# untitled.net
KiCad netlist of a schematic drawn in EAGLE
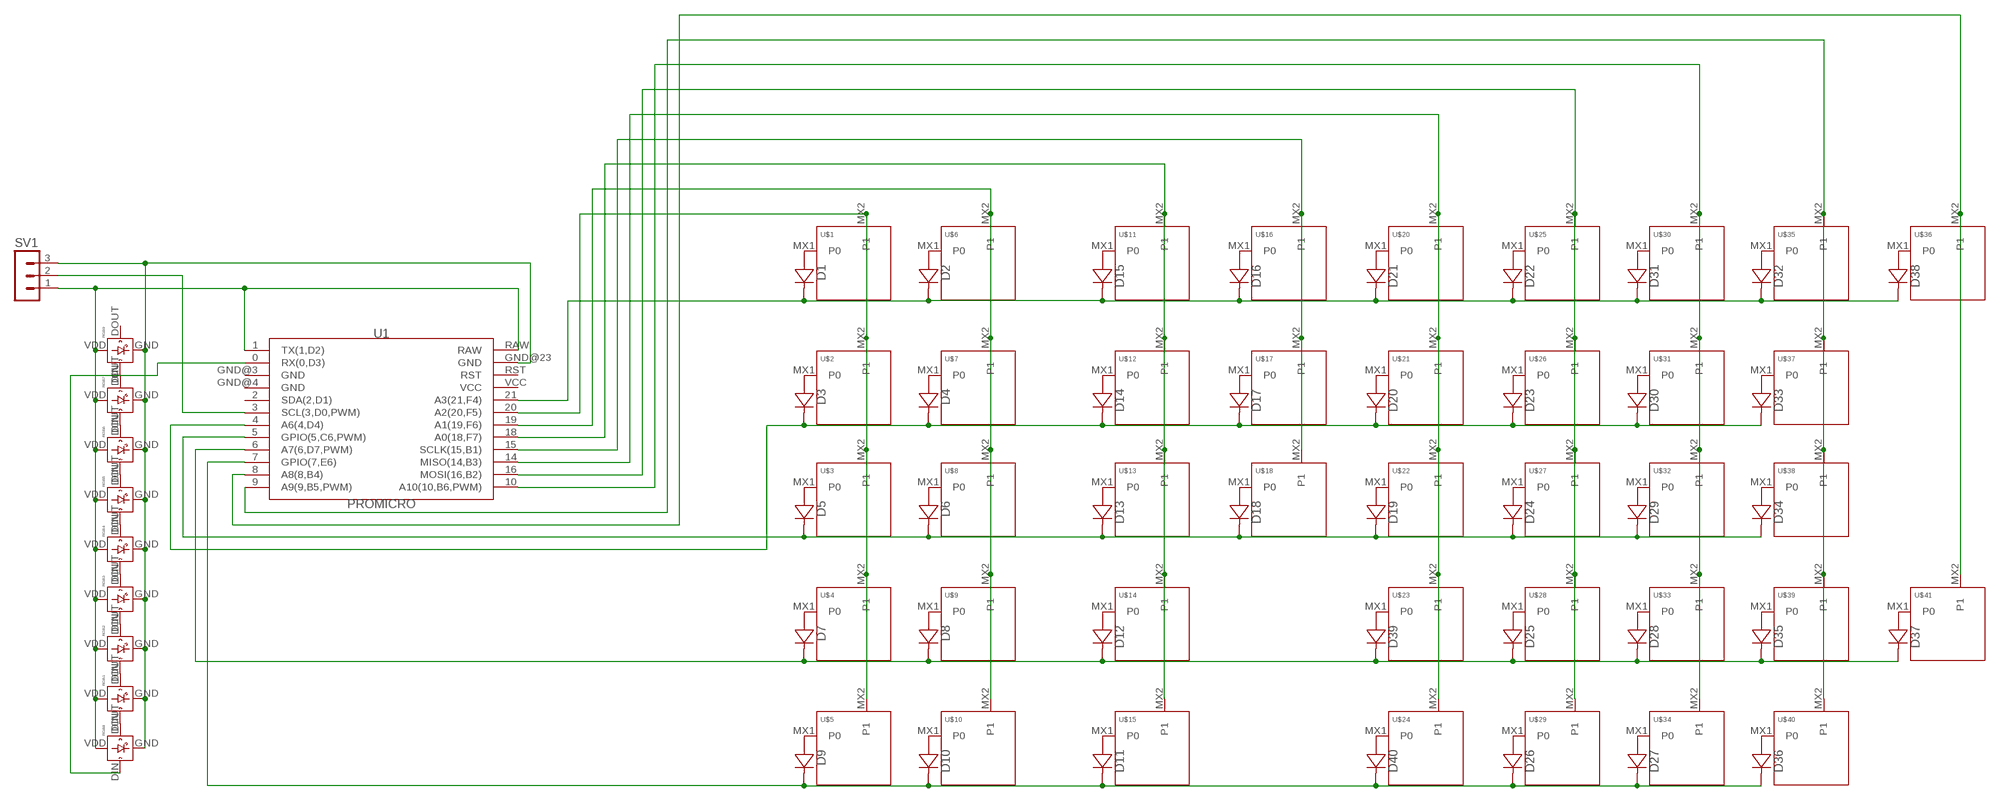
[diagram p0: schematic, sheet 1]

(export (version "E")
  (design (tool "Eeschema 10.0.6"))
  (components
    (comp (ref "D1")
      (value "DIODE-SOD-123")
      (footprint "eagle-import:SOD-123")
      (libsource (lib "eagle-import") (part "DIODE-SOD-123"))
    )
    (comp (ref "D2")
      (value "DIODE-SOD-123")
      (footprint "eagle-import:SOD-123")
      (libsource (lib "eagle-import") (part "DIODE-SOD-123"))
    )
    (comp (ref "D3")
      (value "DIODE-SOD-123")
      (footprint "eagle-import:SOD-123")
      (libsource (lib "eagle-import") (part "DIODE-SOD-123"))
    )
    (comp (ref "D4")
      (value "DIODE-SOD-123")
      (footprint "eagle-import:SOD-123")
      (libsource (lib "eagle-import") (part "DIODE-SOD-123"))
    )
    (comp (ref "D5")
      (value "DIODE-SOD-123")
      (footprint "eagle-import:SOD-123")
      (libsource (lib "eagle-import") (part "DIODE-SOD-123"))
    )
    (comp (ref "D6")
      (value "DIODE-SOD-123")
      (footprint "eagle-import:SOD-123")
      (libsource (lib "eagle-import") (part "DIODE-SOD-123"))
    )
    (comp (ref "D7")
      (value "DIODE-SOD-123")
      (footprint "eagle-import:SOD-123")
      (libsource (lib "eagle-import") (part "DIODE-SOD-123"))
    )
    (comp (ref "D8")
      (value "DIODE-SOD-123")
      (footprint "eagle-import:SOD-123")
      (libsource (lib "eagle-import") (part "DIODE-SOD-123"))
    )
    (comp (ref "D9")
      (value "DIODE-SOD-123")
      (footprint "eagle-import:SOD-123")
      (libsource (lib "eagle-import") (part "DIODE-SOD-123"))
    )
    (comp (ref "D10")
      (value "DIODE-SOD-123")
      (footprint "eagle-import:SOD-123")
      (libsource (lib "eagle-import") (part "DIODE-SOD-123"))
    )
    (comp (ref "D11")
      (value "DIODE-SOD-123")
      (footprint "eagle-import:SOD-123")
      (libsource (lib "eagle-import") (part "DIODE-SOD-123"))
    )
    (comp (ref "D12")
      (value "DIODE-SOD-123")
      (footprint "eagle-import:SOD-123")
      (libsource (lib "eagle-import") (part "DIODE-SOD-123"))
    )
    (comp (ref "D13")
      (value "DIODE-SOD-123")
      (footprint "eagle-import:SOD-123")
      (libsource (lib "eagle-import") (part "DIODE-SOD-123"))
    )
    (comp (ref "D14")
      (value "DIODE-SOD-123")
      (footprint "eagle-import:SOD-123")
      (libsource (lib "eagle-import") (part "DIODE-SOD-123"))
    )
    (comp (ref "D15")
      (value "DIODE-SOD-123")
      (footprint "eagle-import:SOD-123")
      (libsource (lib "eagle-import") (part "DIODE-SOD-123"))
    )
    (comp (ref "D16")
      (value "DIODE-SOD-123")
      (footprint "eagle-import:SOD-123")
      (libsource (lib "eagle-import") (part "DIODE-SOD-123"))
    )
    (comp (ref "D17")
      (value "DIODE-SOD-123")
      (footprint "eagle-import:SOD-123")
      (libsource (lib "eagle-import") (part "DIODE-SOD-123"))
    )
    (comp (ref "D18")
      (value "DIODE-SOD-123")
      (footprint "eagle-import:SOD-123")
      (libsource (lib "eagle-import") (part "DIODE-SOD-123"))
    )
    (comp (ref "D19")
      (value "DIODE-SOD-123")
      (footprint "eagle-import:SOD-123")
      (libsource (lib "eagle-import") (part "DIODE-SOD-123"))
    )
    (comp (ref "D20")
      (value "DIODE-SOD-123")
      (footprint "eagle-import:SOD-123")
      (libsource (lib "eagle-import") (part "DIODE-SOD-123"))
    )
    (comp (ref "D21")
      (value "DIODE-SOD-123")
      (footprint "eagle-import:SOD-123")
      (libsource (lib "eagle-import") (part "DIODE-SOD-123"))
    )
    (comp (ref "D22")
      (value "DIODE-SOD-123")
      (footprint "eagle-import:SOD-123")
      (libsource (lib "eagle-import") (part "DIODE-SOD-123"))
    )
    (comp (ref "D23")
      (value "DIODE-SOD-123")
      (footprint "eagle-import:SOD-123")
      (libsource (lib "eagle-import") (part "DIODE-SOD-123"))
    )
    (comp (ref "D24")
      (value "DIODE-SOD-123")
      (footprint "eagle-import:SOD-123")
      (libsource (lib "eagle-import") (part "DIODE-SOD-123"))
    )
    (comp (ref "D25")
      (value "DIODE-SOD-123")
      (footprint "eagle-import:SOD-123")
      (libsource (lib "eagle-import") (part "DIODE-SOD-123"))
    )
    (comp (ref "D26")
      (value "DIODE-SOD-123")
      (footprint "eagle-import:SOD-123")
      (libsource (lib "eagle-import") (part "DIODE-SOD-123"))
    )
    (comp (ref "D27")
      (value "DIODE-SOD-123")
      (footprint "eagle-import:SOD-123")
      (libsource (lib "eagle-import") (part "DIODE-SOD-123"))
    )
    (comp (ref "D28")
      (value "DIODE-SOD-123")
      (footprint "eagle-import:SOD-123")
      (libsource (lib "eagle-import") (part "DIODE-SOD-123"))
    )
    (comp (ref "D29")
      (value "DIODE-SOD-123")
      (footprint "eagle-import:SOD-123")
      (libsource (lib "eagle-import") (part "DIODE-SOD-123"))
    )
    (comp (ref "D30")
      (value "DIODE-SOD-123")
      (footprint "eagle-import:SOD-123")
      (libsource (lib "eagle-import") (part "DIODE-SOD-123"))
    )
    (comp (ref "D31")
      (value "DIODE-SOD-123")
      (footprint "eagle-import:SOD-123")
      (libsource (lib "eagle-import") (part "DIODE-SOD-123"))
    )
    (comp (ref "D32")
      (value "DIODE-SOD-123")
      (footprint "eagle-import:SOD-123")
      (libsource (lib "eagle-import") (part "DIODE-SOD-123"))
    )
    (comp (ref "D33")
      (value "DIODE-SOD-123")
      (footprint "eagle-import:SOD-123")
      (libsource (lib "eagle-import") (part "DIODE-SOD-123"))
    )
    (comp (ref "D34")
      (value "DIODE-SOD-123")
      (footprint "eagle-import:SOD-123")
      (libsource (lib "eagle-import") (part "DIODE-SOD-123"))
    )
    (comp (ref "D35")
      (value "DIODE-SOD-123")
      (footprint "eagle-import:SOD-123")
      (libsource (lib "eagle-import") (part "DIODE-SOD-123"))
    )
    (comp (ref "D36")
      (value "DIODE-SOD-123")
      (footprint "eagle-import:SOD-123")
      (libsource (lib "eagle-import") (part "DIODE-SOD-123"))
    )
    (comp (ref "D37")
      (value "DIODE-SOD-123")
      (footprint "eagle-import:SOD-123")
      (libsource (lib "eagle-import") (part "DIODE-SOD-123"))
    )
    (comp (ref "D38")
      (value "DIODE-SOD-123")
      (footprint "eagle-import:SOD-123")
      (libsource (lib "eagle-import") (part "DIODE-SOD-123"))
    )
    (comp (ref "D39")
      (value "DIODE-SOD-123")
      (footprint "eagle-import:SOD-123")
      (libsource (lib "eagle-import") (part "DIODE-SOD-123"))
    )
    (comp (ref "D40")
      (value "DIODE-SOD-123")
      (footprint "eagle-import:SOD-123")
      (libsource (lib "eagle-import") (part "DIODE-SOD-123"))
    )
    (comp (ref "RGB1")
      (value "WS2812B-MINI")
      (footprint "eagle-import:WS2812B-MINI")
      (libsource (lib "eagle-import") (part "WS2812B-MINI"))
    )
    (comp (ref "RGB2")
      (value "WS2812B-MINI")
      (footprint "eagle-import:WS2812B-MINI")
      (libsource (lib "eagle-import") (part "WS2812B-MINI"))
    )
    (comp (ref "RGB3")
      (value "WS2812B-MINI")
      (footprint "eagle-import:WS2812B-MINI")
      (libsource (lib "eagle-import") (part "WS2812B-MINI"))
    )
    (comp (ref "RGB4")
      (value "WS2812B-MINI")
      (footprint "eagle-import:WS2812B-MINI")
      (libsource (lib "eagle-import") (part "WS2812B-MINI"))
    )
    (comp (ref "RGB5")
      (value "WS2812B-MINI")
      (footprint "eagle-import:WS2812B-MINI")
      (libsource (lib "eagle-import") (part "WS2812B-MINI"))
    )
    (comp (ref "RGB6")
      (value "WS2812B-MINI")
      (footprint "eagle-import:WS2812B-MINI")
      (libsource (lib "eagle-import") (part "WS2812B-MINI"))
    )
    (comp (ref "RGB7")
      (value "WS2812B-MINI")
      (footprint "eagle-import:WS2812B-MINI")
      (libsource (lib "eagle-import") (part "WS2812B-MINI"))
    )
    (comp (ref "RGB8")
      (value "WS2812B-MINI")
      (footprint "eagle-import:WS2812B-MINI")
      (libsource (lib "eagle-import") (part "WS2812B-MINI"))
    )
    (comp (ref "RGB9")
      (value "WS2812B-MINI")
      (footprint "eagle-import:WS2812B-MINI")
      (libsource (lib "eagle-import") (part "WS2812B-MINI"))
    )
    (comp (ref "SV1")
      (value "MA03-1")
      (footprint "eagle-import:MA03-1")
      (libsource (lib "eagle-import") (part "MA03-1"))
    )
    (comp (ref "U$1")
      (value "KEYSWITCH-PLAIN-MX-1U")
      (footprint "eagle-import:MX-1U")
      (libsource (lib "eagle-import") (part "KEYSWITCH-PLAIN-MX-1U"))
    )
    (comp (ref "U$2")
      (value "KEYSWITCH-PLAIN-MX-1U")
      (footprint "eagle-import:MX-1U")
      (libsource (lib "eagle-import") (part "KEYSWITCH-PLAIN-MX-1U"))
    )
    (comp (ref "U$3")
      (value "KEYSWITCH-PLAIN-MX-1U")
      (footprint "eagle-import:MX-1U")
      (libsource (lib "eagle-import") (part "KEYSWITCH-PLAIN-MX-1U"))
    )
    (comp (ref "U$4")
      (value "KEYSWITCH-PLAIN-MX-1U")
      (footprint "eagle-import:MX-1U")
      (libsource (lib "eagle-import") (part "KEYSWITCH-PLAIN-MX-1U"))
    )
    (comp (ref "U$5")
      (value "KEYSWITCH-PLAIN-MX-1U")
      (footprint "eagle-import:MX-1U")
      (libsource (lib "eagle-import") (part "KEYSWITCH-PLAIN-MX-1U"))
    )
    (comp (ref "U$6")
      (value "KEYSWITCH-PLAIN-MX-1U")
      (footprint "eagle-import:MX-1U")
      (libsource (lib "eagle-import") (part "KEYSWITCH-PLAIN-MX-1U"))
    )
    (comp (ref "U$7")
      (value "KEYSWITCH-PLAIN-MX-1U")
      (footprint "eagle-import:MX-1U")
      (libsource (lib "eagle-import") (part "KEYSWITCH-PLAIN-MX-1U"))
    )
    (comp (ref "U$8")
      (value "KEYSWITCH-PLAIN-MX-1U")
      (footprint "eagle-import:MX-1U")
      (libsource (lib "eagle-import") (part "KEYSWITCH-PLAIN-MX-1U"))
    )
    (comp (ref "U$9")
      (value "KEYSWITCH-PLAIN-MX-1U")
      (footprint "eagle-import:MX-1U")
      (libsource (lib "eagle-import") (part "KEYSWITCH-PLAIN-MX-1U"))
    )
    (comp (ref "U$10")
      (value "KEYSWITCH-PLAIN-MX-1U")
      (footprint "eagle-import:MX-1U")
      (libsource (lib "eagle-import") (part "KEYSWITCH-PLAIN-MX-1U"))
    )
    (comp (ref "U$11")
      (value "KEYSWITCH-PLAIN-MX-1U")
      (footprint "eagle-import:MX-1U")
      (libsource (lib "eagle-import") (part "KEYSWITCH-PLAIN-MX-1U"))
    )
    (comp (ref "U$12")
      (value "KEYSWITCH-PLAIN-MX-1U")
      (footprint "eagle-import:MX-1U")
      (libsource (lib "eagle-import") (part "KEYSWITCH-PLAIN-MX-1U"))
    )
    (comp (ref "U$13")
      (value "KEYSWITCH-PLAIN-MX-1U")
      (footprint "eagle-import:MX-1U")
      (libsource (lib "eagle-import") (part "KEYSWITCH-PLAIN-MX-1U"))
    )
    (comp (ref "U$14")
      (value "KEYSWITCH-PLAIN-MX-1U")
      (footprint "eagle-import:MX-1U")
      (libsource (lib "eagle-import") (part "KEYSWITCH-PLAIN-MX-1U"))
    )
    (comp (ref "U$15")
      (value "KEYSWITCH-PLAIN-MX-1U")
      (footprint "eagle-import:MX-1U")
      (libsource (lib "eagle-import") (part "KEYSWITCH-PLAIN-MX-1U"))
    )
    (comp (ref "U$16")
      (value "KEYSWITCH-PLAIN-MX-1U")
      (footprint "eagle-import:MX-1U")
      (libsource (lib "eagle-import") (part "KEYSWITCH-PLAIN-MX-1U"))
    )
    (comp (ref "U$17")
      (value "KEYSWITCH-PLAIN-MX-1U")
      (footprint "eagle-import:MX-1U")
      (libsource (lib "eagle-import") (part "KEYSWITCH-PLAIN-MX-1U"))
    )
    (comp (ref "U$18")
      (value "KEYSWITCH-PLAIN-MX-1U")
      (footprint "eagle-import:MX-1U")
      (libsource (lib "eagle-import") (part "KEYSWITCH-PLAIN-MX-1U"))
    )
    (comp (ref "U$20")
      (value "KEYSWITCH-PLAIN-MX-1U")
      (footprint "eagle-import:MX-1U")
      (libsource (lib "eagle-import") (part "KEYSWITCH-PLAIN-MX-1U"))
    )
    (comp (ref "U$21")
      (value "KEYSWITCH-PLAIN-MX-1U")
      (footprint "eagle-import:MX-1U")
      (libsource (lib "eagle-import") (part "KEYSWITCH-PLAIN-MX-1U"))
    )
    (comp (ref "U$22")
      (value "KEYSWITCH-PLAIN-MX-1U")
      (footprint "eagle-import:MX-1U")
      (libsource (lib "eagle-import") (part "KEYSWITCH-PLAIN-MX-1U"))
    )
    (comp (ref "U$23")
      (value "KEYSWITCH-PLAIN-MX-1U")
      (footprint "eagle-import:MX-1U")
      (libsource (lib "eagle-import") (part "KEYSWITCH-PLAIN-MX-1U"))
    )
    (comp (ref "U$24")
      (value "KEYSWITCH-PLAIN-MX-1U")
      (footprint "eagle-import:MX-1U")
      (libsource (lib "eagle-import") (part "KEYSWITCH-PLAIN-MX-1U"))
    )
    (comp (ref "U$25")
      (value "KEYSWITCH-PLAIN-MX-1U")
      (footprint "eagle-import:MX-1U")
      (libsource (lib "eagle-import") (part "KEYSWITCH-PLAIN-MX-1U"))
    )
    (comp (ref "U$26")
      (value "KEYSWITCH-PLAIN-MX-1U")
      (footprint "eagle-import:MX-1U")
      (libsource (lib "eagle-import") (part "KEYSWITCH-PLAIN-MX-1U"))
    )
    (comp (ref "U$27")
      (value "KEYSWITCH-PLAIN-MX-1U")
      (footprint "eagle-import:MX-1U")
      (libsource (lib "eagle-import") (part "KEYSWITCH-PLAIN-MX-1U"))
    )
    (comp (ref "U$28")
      (value "KEYSWITCH-PLAIN-MX-1U")
      (footprint "eagle-import:MX-1U")
      (libsource (lib "eagle-import") (part "KEYSWITCH-PLAIN-MX-1U"))
    )
    (comp (ref "U$29")
      (value "KEYSWITCH-PLAIN-MX-1U")
      (footprint "eagle-import:MX-1U")
      (libsource (lib "eagle-import") (part "KEYSWITCH-PLAIN-MX-1U"))
    )
    (comp (ref "U$30")
      (value "KEYSWITCH-PLAIN-MX-1U")
      (footprint "eagle-import:MX-1U")
      (libsource (lib "eagle-import") (part "KEYSWITCH-PLAIN-MX-1U"))
    )
    (comp (ref "U$31")
      (value "KEYSWITCH-PLAIN-MX-1U")
      (footprint "eagle-import:MX-1U")
      (libsource (lib "eagle-import") (part "KEYSWITCH-PLAIN-MX-1U"))
    )
    (comp (ref "U$32")
      (value "KEYSWITCH-PLAIN-MX-1U")
      (footprint "eagle-import:MX-1U")
      (libsource (lib "eagle-import") (part "KEYSWITCH-PLAIN-MX-1U"))
    )
    (comp (ref "U$33")
      (value "KEYSWITCH-PLAIN-MX-1U")
      (footprint "eagle-import:MX-1U")
      (libsource (lib "eagle-import") (part "KEYSWITCH-PLAIN-MX-1U"))
    )
    (comp (ref "U$34")
      (value "KEYSWITCH-PLAIN-MX-1U")
      (footprint "eagle-import:MX-1U")
      (libsource (lib "eagle-import") (part "KEYSWITCH-PLAIN-MX-1U"))
    )
    (comp (ref "U$35")
      (value "KEYSWITCH-PLAIN-MX-1U")
      (footprint "eagle-import:MX-1U")
      (libsource (lib "eagle-import") (part "KEYSWITCH-PLAIN-MX-1U"))
    )
    (comp (ref "U$36")
      (value "KEYSWITCH-PLAIN-MX-1U")
      (footprint "eagle-import:MX-1U")
      (libsource (lib "eagle-import") (part "KEYSWITCH-PLAIN-MX-1U"))
    )
    (comp (ref "U$37")
      (value "KEYSWITCH-PLAIN-MX-1U")
      (footprint "eagle-import:MX-1U")
      (libsource (lib "eagle-import") (part "KEYSWITCH-PLAIN-MX-1U"))
    )
    (comp (ref "U$38")
      (value "KEYSWITCH-PLAIN-MX-1U")
      (footprint "eagle-import:MX-1U")
      (libsource (lib "eagle-import") (part "KEYSWITCH-PLAIN-MX-1U"))
    )
    (comp (ref "U$39")
      (value "KEYSWITCH-PLAIN-MX-1U")
      (footprint "eagle-import:MX-1U")
      (libsource (lib "eagle-import") (part "KEYSWITCH-PLAIN-MX-1U"))
    )
    (comp (ref "U$40")
      (value "KEYSWITCH-PLAIN-MX-1U")
      (footprint "eagle-import:MX-1U")
      (libsource (lib "eagle-import") (part "KEYSWITCH-PLAIN-MX-1U"))
    )
    (comp (ref "U$41")
      (value "KEYSWITCH-PLAIN-MX-1U")
      (footprint "eagle-import:MX-1U")
      (libsource (lib "eagle-import") (part "KEYSWITCH-PLAIN-MX-1U"))
    )
    (comp (ref "U1")
      (value "PROMICRO")
      (footprint "eagle-import:PROMICRO")
      (libsource (lib "eagle-import") (part "PROMICRO"))
    )
  )
  (nets
    (net (code "1") (name "Net-(RGB1-PadDIN)") (class "Default")
      (node (ref "RGB1") (pin "DIN") (pinfunction "DIN_DIN") (pintype "input"))
      (node (ref "RGB8") (pin "DOUT") (pinfunction "DOUT_DOUT") (pintype "output"))
    )
    (net (code "2") (name "Net-(RGB1-PadDOUT)") (class "Default")
      (node (ref "RGB1") (pin "DOUT") (pinfunction "DOUT_DOUT") (pintype "output"))
      (node (ref "RGB2") (pin "DIN") (pinfunction "DIN_DIN") (pintype "input"))
    )
    (net (code "3") (name "Net-(RGB1-PadGND)") (class "Default")
      (node (ref "RGB1") (pin "GND") (pinfunction "GND_GND") (pintype "bidirectional"))
      (node (ref "RGB2") (pin "GND") (pinfunction "GND_GND") (pintype "bidirectional"))
      (node (ref "RGB3") (pin "GND") (pinfunction "GND_GND") (pintype "bidirectional"))
      (node (ref "RGB4") (pin "GND") (pinfunction "GND_GND") (pintype "bidirectional"))
      (node (ref "RGB5") (pin "GND") (pinfunction "GND_GND") (pintype "bidirectional"))
      (node (ref "RGB6") (pin "GND") (pinfunction "GND_GND") (pintype "bidirectional"))
      (node (ref "RGB7") (pin "GND") (pinfunction "GND_GND") (pintype "bidirectional"))
      (node (ref "RGB8") (pin "GND") (pinfunction "GND_GND") (pintype "bidirectional"))
      (node (ref "RGB9") (pin "GND") (pinfunction "GND_GND") (pintype "bidirectional"))
      (node (ref "SV1") (pin "3") (pinfunction "3_3") (pintype "passive"))
      (node (ref "U1") (pin "GND@23") (pinfunction "GND_GND@23") (pintype "bidirectional"))
    )
    (net (code "4") (name "Net-(RGB2-PadDOUT)") (class "Default")
      (node (ref "RGB2") (pin "DOUT") (pinfunction "DOUT_DOUT") (pintype "output"))
      (node (ref "RGB3") (pin "DIN") (pinfunction "DIN_DIN") (pintype "input"))
    )
    (net (code "5") (name "Net-(RGB3-PadDOUT)") (class "Default")
      (node (ref "RGB3") (pin "DOUT") (pinfunction "DOUT_DOUT") (pintype "output"))
      (node (ref "RGB4") (pin "DIN") (pinfunction "DIN_DIN") (pintype "input"))
    )
    (net (code "6") (name "Net-(RGB4-PadDOUT)") (class "Default")
      (node (ref "RGB4") (pin "DOUT") (pinfunction "DOUT_DOUT") (pintype "output"))
      (node (ref "RGB5") (pin "DIN") (pinfunction "DIN_DIN") (pintype "input"))
    )
    (net (code "7") (name "Net-(RGB5-PadDOUT)") (class "Default")
      (node (ref "RGB5") (pin "DOUT") (pinfunction "DOUT_DOUT") (pintype "output"))
      (node (ref "RGB6") (pin "DIN") (pinfunction "DIN_DIN") (pintype "input"))
    )
    (net (code "8") (name "Net-(RGB6-PadDOUT)") (class "Default")
      (node (ref "RGB6") (pin "DOUT") (pinfunction "DOUT_DOUT") (pintype "output"))
      (node (ref "RGB7") (pin "DIN") (pinfunction "DIN_DIN") (pintype "input"))
    )
    (net (code "9") (name "Net-(RGB7-PadDOUT)") (class "Default")
      (node (ref "RGB7") (pin "DOUT") (pinfunction "DOUT_DOUT") (pintype "output"))
      (node (ref "RGB9") (pin "DIN") (pinfunction "DIN_DIN") (pintype "input"))
    )
    (net (code "10") (name "Net-(U$1-P0)") (class "Default")
      (node (ref "D1") (pin "A") (pinfunction "A_A") (pintype "passive"))
      (node (ref "U$1") (pin "MX1") (pinfunction "P0_MX1") (pintype "bidirectional"))
    )
    (net (code "11") (name "Net-(U$1-P1)") (class "Default")
      (node (ref "U$1") (pin "MX2") (pinfunction "P1_MX2") (pintype "bidirectional"))
      (node (ref "U$2") (pin "MX2") (pinfunction "P1_MX2") (pintype "bidirectional"))
      (node (ref "U$3") (pin "MX2") (pinfunction "P1_MX2") (pintype "bidirectional"))
      (node (ref "U$4") (pin "MX2") (pinfunction "P1_MX2") (pintype "bidirectional"))
      (node (ref "U$5") (pin "MX2") (pinfunction "P1_MX2") (pintype "bidirectional"))
      (node (ref "U1") (pin "20") (pinfunction "A2(20,F5)_20") (pintype "bidirectional"))
    )
    (net (code "12") (name "Net-(U$2-P0)") (class "Default")
      (node (ref "D3") (pin "A") (pinfunction "A_A") (pintype "passive"))
      (node (ref "U$2") (pin "MX1") (pinfunction "P0_MX1") (pintype "bidirectional"))
    )
    (net (code "13") (name "Net-(U$3-P0)") (class "Default")
      (node (ref "D5") (pin "A") (pinfunction "A_A") (pintype "passive"))
      (node (ref "U$3") (pin "MX1") (pinfunction "P0_MX1") (pintype "bidirectional"))
    )
    (net (code "14") (name "Net-(U$4-P0)") (class "Default")
      (node (ref "D7") (pin "A") (pinfunction "A_A") (pintype "passive"))
      (node (ref "U$4") (pin "MX1") (pinfunction "P0_MX1") (pintype "bidirectional"))
    )
    (net (code "15") (name "Net-(U$5-P0)") (class "Default")
      (node (ref "D9") (pin "A") (pinfunction "A_A") (pintype "passive"))
      (node (ref "U$5") (pin "MX1") (pinfunction "P0_MX1") (pintype "bidirectional"))
    )
    (net (code "16") (name "Net-(U$6-P0)") (class "Default")
      (node (ref "D2") (pin "A") (pinfunction "A_A") (pintype "passive"))
      (node (ref "U$6") (pin "MX1") (pinfunction "P0_MX1") (pintype "bidirectional"))
    )
    (net (code "17") (name "Net-(U$7-P0)") (class "Default")
      (node (ref "D4") (pin "A") (pinfunction "A_A") (pintype "passive"))
      (node (ref "U$7") (pin "MX1") (pinfunction "P0_MX1") (pintype "bidirectional"))
    )
    (net (code "18") (name "Net-(U$8-P0)") (class "Default")
      (node (ref "D6") (pin "A") (pinfunction "A_A") (pintype "passive"))
      (node (ref "U$8") (pin "MX1") (pinfunction "P0_MX1") (pintype "bidirectional"))
    )
    (net (code "19") (name "Net-(U$9-P0)") (class "Default")
      (node (ref "D8") (pin "A") (pinfunction "A_A") (pintype "passive"))
      (node (ref "U$9") (pin "MX1") (pinfunction "P0_MX1") (pintype "bidirectional"))
    )
    (net (code "20") (name "Net-(U$10-P0)") (class "Default")
      (node (ref "D10") (pin "A") (pinfunction "A_A") (pintype "passive"))
      (node (ref "U$10") (pin "MX1") (pinfunction "P0_MX1") (pintype "bidirectional"))
    )
    (net (code "21") (name "Net-(U$10-P1)") (class "Default")
      (node (ref "U$10") (pin "MX2") (pinfunction "P1_MX2") (pintype "bidirectional"))
      (node (ref "U$6") (pin "MX2") (pinfunction "P1_MX2") (pintype "bidirectional"))
      (node (ref "U$7") (pin "MX2") (pinfunction "P1_MX2") (pintype "bidirectional"))
      (node (ref "U$8") (pin "MX2") (pinfunction "P1_MX2") (pintype "bidirectional"))
      (node (ref "U$9") (pin "MX2") (pinfunction "P1_MX2") (pintype "bidirectional"))
      (node (ref "U1") (pin "19") (pinfunction "A1(19,F6)_19") (pintype "bidirectional"))
    )
    (net (code "22") (name "Net-(U$11-P0)") (class "Default")
      (node (ref "D15") (pin "A") (pinfunction "A_A") (pintype "passive"))
      (node (ref "U$11") (pin "MX1") (pinfunction "P0_MX1") (pintype "bidirectional"))
    )
    (net (code "23") (name "Net-(U$11-P1)") (class "Default")
      (node (ref "U$11") (pin "MX2") (pinfunction "P1_MX2") (pintype "bidirectional"))
      (node (ref "U$12") (pin "MX2") (pinfunction "P1_MX2") (pintype "bidirectional"))
      (node (ref "U$13") (pin "MX2") (pinfunction "P1_MX2") (pintype "bidirectional"))
      (node (ref "U$14") (pin "MX2") (pinfunction "P1_MX2") (pintype "bidirectional"))
      (node (ref "U$15") (pin "MX2") (pinfunction "P1_MX2") (pintype "bidirectional"))
      (node (ref "U1") (pin "18") (pinfunction "A0(18,F7)_18") (pintype "bidirectional"))
    )
    (net (code "24") (name "Net-(U$12-P0)") (class "Default")
      (node (ref "D14") (pin "A") (pinfunction "A_A") (pintype "passive"))
      (node (ref "U$12") (pin "MX1") (pinfunction "P0_MX1") (pintype "bidirectional"))
    )
    (net (code "25") (name "Net-(U$13-P0)") (class "Default")
      (node (ref "D13") (pin "A") (pinfunction "A_A") (pintype "passive"))
      (node (ref "U$13") (pin "MX1") (pinfunction "P0_MX1") (pintype "bidirectional"))
    )
    (net (code "26") (name "Net-(U$14-P0)") (class "Default")
      (node (ref "D12") (pin "A") (pinfunction "A_A") (pintype "passive"))
      (node (ref "U$14") (pin "MX1") (pinfunction "P0_MX1") (pintype "bidirectional"))
    )
    (net (code "27") (name "Net-(U$15-P0)") (class "Default")
      (node (ref "D11") (pin "A") (pinfunction "A_A") (pintype "passive"))
      (node (ref "U$15") (pin "MX1") (pinfunction "P0_MX1") (pintype "bidirectional"))
    )
    (net (code "28") (name "Net-(U$16-P0)") (class "Default")
      (node (ref "D16") (pin "A") (pinfunction "A_A") (pintype "passive"))
      (node (ref "U$16") (pin "MX1") (pinfunction "P0_MX1") (pintype "bidirectional"))
    )
    (net (code "29") (name "Net-(U$16-P1)") (class "Default")
      (node (ref "U$16") (pin "MX2") (pinfunction "P1_MX2") (pintype "bidirectional"))
      (node (ref "U$17") (pin "MX2") (pinfunction "P1_MX2") (pintype "bidirectional"))
      (node (ref "U$18") (pin "MX2") (pinfunction "P1_MX2") (pintype "bidirectional"))
      (node (ref "U1") (pin "15") (pinfunction "SCLK(15,B1)_15") (pintype "bidirectional"))
    )
    (net (code "30") (name "Net-(U$17-P0)") (class "Default")
      (node (ref "D17") (pin "A") (pinfunction "A_A") (pintype "passive"))
      (node (ref "U$17") (pin "MX1") (pinfunction "P0_MX1") (pintype "bidirectional"))
    )
    (net (code "31") (name "Net-(U$18-P0)") (class "Default")
      (node (ref "D18") (pin "A") (pinfunction "A_A") (pintype "passive"))
      (node (ref "U$18") (pin "MX1") (pinfunction "P0_MX1") (pintype "bidirectional"))
    )
    (net (code "32") (name "Net-(U$20-P0)") (class "Default")
      (node (ref "D21") (pin "A") (pinfunction "A_A") (pintype "passive"))
      (node (ref "U$20") (pin "MX1") (pinfunction "P0_MX1") (pintype "bidirectional"))
    )
    (net (code "33") (name "Net-(U$20-P1)") (class "Default")
      (node (ref "U$20") (pin "MX2") (pinfunction "P1_MX2") (pintype "bidirectional"))
      (node (ref "U$21") (pin "MX2") (pinfunction "P1_MX2") (pintype "bidirectional"))
      (node (ref "U$22") (pin "MX2") (pinfunction "P1_MX2") (pintype "bidirectional"))
      (node (ref "U$23") (pin "MX2") (pinfunction "P1_MX2") (pintype "bidirectional"))
      (node (ref "U$24") (pin "MX2") (pinfunction "P1_MX2") (pintype "bidirectional"))
      (node (ref "U1") (pin "14") (pinfunction "MISO(14,B3)_14") (pintype "bidirectional"))
    )
    (net (code "34") (name "Net-(U$21-P0)") (class "Default")
      (node (ref "D20") (pin "A") (pinfunction "A_A") (pintype "passive"))
      (node (ref "U$21") (pin "MX1") (pinfunction "P0_MX1") (pintype "bidirectional"))
    )
    (net (code "35") (name "Net-(U$22-P0)") (class "Default")
      (node (ref "D19") (pin "A") (pinfunction "A_A") (pintype "passive"))
      (node (ref "U$22") (pin "MX1") (pinfunction "P0_MX1") (pintype "bidirectional"))
    )
    (net (code "36") (name "Net-(U$23-P0)") (class "Default")
      (node (ref "D39") (pin "A") (pinfunction "A_A") (pintype "passive"))
      (node (ref "U$23") (pin "MX1") (pinfunction "P0_MX1") (pintype "bidirectional"))
    )
    (net (code "37") (name "Net-(U$24-P0)") (class "Default")
      (node (ref "D40") (pin "A") (pinfunction "A_A") (pintype "passive"))
      (node (ref "U$24") (pin "MX1") (pinfunction "P0_MX1") (pintype "bidirectional"))
    )
    (net (code "38") (name "Net-(U$25-P0)") (class "Default")
      (node (ref "D22") (pin "A") (pinfunction "A_A") (pintype "passive"))
      (node (ref "U$25") (pin "MX1") (pinfunction "P0_MX1") (pintype "bidirectional"))
    )
    (net (code "39") (name "Net-(U$25-P1)") (class "Default")
      (node (ref "U$25") (pin "MX2") (pinfunction "P1_MX2") (pintype "bidirectional"))
      (node (ref "U$26") (pin "MX2") (pinfunction "P1_MX2") (pintype "bidirectional"))
      (node (ref "U$27") (pin "MX2") (pinfunction "P1_MX2") (pintype "bidirectional"))
      (node (ref "U$28") (pin "MX2") (pinfunction "P1_MX2") (pintype "bidirectional"))
      (node (ref "U$29") (pin "MX2") (pinfunction "P1_MX2") (pintype "bidirectional"))
      (node (ref "U1") (pin "16") (pinfunction "MOSI(16,B2)_16") (pintype "bidirectional"))
    )
    (net (code "40") (name "Net-(U$26-P0)") (class "Default")
      (node (ref "D23") (pin "A") (pinfunction "A_A") (pintype "passive"))
      (node (ref "U$26") (pin "MX1") (pinfunction "P0_MX1") (pintype "bidirectional"))
    )
    (net (code "41") (name "Net-(U$27-P0)") (class "Default")
      (node (ref "D24") (pin "A") (pinfunction "A_A") (pintype "passive"))
      (node (ref "U$27") (pin "MX1") (pinfunction "P0_MX1") (pintype "bidirectional"))
    )
    (net (code "42") (name "Net-(U$28-P0)") (class "Default")
      (node (ref "D25") (pin "A") (pinfunction "A_A") (pintype "passive"))
      (node (ref "U$28") (pin "MX1") (pinfunction "P0_MX1") (pintype "bidirectional"))
    )
    (net (code "43") (name "Net-(U$29-P0)") (class "Default")
      (node (ref "D26") (pin "A") (pinfunction "A_A") (pintype "passive"))
      (node (ref "U$29") (pin "MX1") (pinfunction "P0_MX1") (pintype "bidirectional"))
    )
    (net (code "44") (name "Net-(U$30-P0)") (class "Default")
      (node (ref "D31") (pin "A") (pinfunction "A_A") (pintype "passive"))
      (node (ref "U$30") (pin "MX1") (pinfunction "P0_MX1") (pintype "bidirectional"))
    )
    (net (code "45") (name "Net-(U$30-P1)") (class "Default")
      (node (ref "U$30") (pin "MX2") (pinfunction "P1_MX2") (pintype "bidirectional"))
      (node (ref "U$31") (pin "MX2") (pinfunction "P1_MX2") (pintype "bidirectional"))
      (node (ref "U$32") (pin "MX2") (pinfunction "P1_MX2") (pintype "bidirectional"))
      (node (ref "U$33") (pin "MX2") (pinfunction "P1_MX2") (pintype "bidirectional"))
      (node (ref "U$34") (pin "MX2") (pinfunction "P1_MX2") (pintype "bidirectional"))
      (node (ref "U1") (pin "10") (pinfunction "A10(10,B6,PWM)_10") (pintype "bidirectional"))
    )
    (net (code "46") (name "Net-(U$31-P0)") (class "Default")
      (node (ref "D30") (pin "A") (pinfunction "A_A") (pintype "passive"))
      (node (ref "U$31") (pin "MX1") (pinfunction "P0_MX1") (pintype "bidirectional"))
    )
    (net (code "47") (name "Net-(U$32-P0)") (class "Default")
      (node (ref "D29") (pin "A") (pinfunction "A_A") (pintype "passive"))
      (node (ref "U$32") (pin "MX1") (pinfunction "P0_MX1") (pintype "bidirectional"))
    )
    (net (code "48") (name "Net-(U$33-P0)") (class "Default")
      (node (ref "D28") (pin "A") (pinfunction "A_A") (pintype "passive"))
      (node (ref "U$33") (pin "MX1") (pinfunction "P0_MX1") (pintype "bidirectional"))
    )
    (net (code "49") (name "Net-(U$34-P0)") (class "Default")
      (node (ref "D27") (pin "A") (pinfunction "A_A") (pintype "passive"))
      (node (ref "U$34") (pin "MX1") (pinfunction "P0_MX1") (pintype "bidirectional"))
    )
    (net (code "50") (name "Net-(U$35-P0)") (class "Default")
      (node (ref "D32") (pin "A") (pinfunction "A_A") (pintype "passive"))
      (node (ref "U$35") (pin "MX1") (pinfunction "P0_MX1") (pintype "bidirectional"))
    )
    (net (code "51") (name "Net-(U$35-P1)") (class "Default")
      (node (ref "U$35") (pin "MX2") (pinfunction "P1_MX2") (pintype "bidirectional"))
      (node (ref "U$37") (pin "MX2") (pinfunction "P1_MX2") (pintype "bidirectional"))
      (node (ref "U$38") (pin "MX2") (pinfunction "P1_MX2") (pintype "bidirectional"))
      (node (ref "U$39") (pin "MX2") (pinfunction "P1_MX2") (pintype "bidirectional"))
      (node (ref "U$40") (pin "MX2") (pinfunction "P1_MX2") (pintype "bidirectional"))
      (node (ref "U1") (pin "9") (pinfunction "A9(9,B5,PWM)_9") (pintype "bidirectional"))
    )
    (net (code "52") (name "Net-(U$36-P0)") (class "Default")
      (node (ref "D38") (pin "A") (pinfunction "A_A") (pintype "passive"))
      (node (ref "U$36") (pin "MX1") (pinfunction "P0_MX1") (pintype "bidirectional"))
    )
    (net (code "53") (name "Net-(U$36-P1)") (class "Default")
      (node (ref "U$36") (pin "MX2") (pinfunction "P1_MX2") (pintype "bidirectional"))
      (node (ref "U$41") (pin "MX2") (pinfunction "P1_MX2") (pintype "bidirectional"))
      (node (ref "U1") (pin "8") (pinfunction "A8(8,B4)_8") (pintype "bidirectional"))
    )
    (net (code "54") (name "Net-(U$37-P0)") (class "Default")
      (node (ref "D33") (pin "A") (pinfunction "A_A") (pintype "passive"))
      (node (ref "U$37") (pin "MX1") (pinfunction "P0_MX1") (pintype "bidirectional"))
    )
    (net (code "55") (name "Net-(U$38-P0)") (class "Default")
      (node (ref "D34") (pin "A") (pinfunction "A_A") (pintype "passive"))
      (node (ref "U$38") (pin "MX1") (pinfunction "P0_MX1") (pintype "bidirectional"))
    )
    (net (code "56") (name "Net-(U$39-P0)") (class "Default")
      (node (ref "D35") (pin "A") (pinfunction "A_A") (pintype "passive"))
      (node (ref "U$39") (pin "MX1") (pinfunction "P0_MX1") (pintype "bidirectional"))
    )
    (net (code "57") (name "Net-(U$40-P0)") (class "Default")
      (node (ref "D36") (pin "A") (pinfunction "A_A") (pintype "passive"))
      (node (ref "U$40") (pin "MX1") (pinfunction "P0_MX1") (pintype "bidirectional"))
    )
    (net (code "58") (name "Net-(U$41-P0)") (class "Default")
      (node (ref "D37") (pin "A") (pinfunction "A_A") (pintype "passive"))
      (node (ref "U$41") (pin "MX1") (pinfunction "P0_MX1") (pintype "bidirectional"))
    )
    (net (code "59") (name "Net-(U1-A3(21,F4))") (class "Default")
      (node (ref "D1") (pin "C") (pinfunction "C_C") (pintype "passive"))
      (node (ref "D15") (pin "C") (pinfunction "C_C") (pintype "passive"))
      (node (ref "D16") (pin "C") (pinfunction "C_C") (pintype "passive"))
      (node (ref "D2") (pin "C") (pinfunction "C_C") (pintype "passive"))
      (node (ref "D21") (pin "C") (pinfunction "C_C") (pintype "passive"))
      (node (ref "D22") (pin "C") (pinfunction "C_C") (pintype "passive"))
      (node (ref "D31") (pin "C") (pinfunction "C_C") (pintype "passive"))
      (node (ref "D32") (pin "C") (pinfunction "C_C") (pintype "passive"))
      (node (ref "D38") (pin "C") (pinfunction "C_C") (pintype "passive"))
      (node (ref "U1") (pin "21") (pinfunction "A3(21,F4)_21") (pintype "bidirectional"))
    )
    (net (code "60") (name "Net-(U1-A6(4,D4))") (class "Default")
      (node (ref "D14") (pin "C") (pinfunction "C_C") (pintype "passive"))
      (node (ref "D17") (pin "C") (pinfunction "C_C") (pintype "passive"))
      (node (ref "D20") (pin "C") (pinfunction "C_C") (pintype "passive"))
      (node (ref "D23") (pin "C") (pinfunction "C_C") (pintype "passive"))
      (node (ref "D3") (pin "C") (pinfunction "C_C") (pintype "passive"))
      (node (ref "D30") (pin "C") (pinfunction "C_C") (pintype "passive"))
      (node (ref "D33") (pin "C") (pinfunction "C_C") (pintype "passive"))
      (node (ref "D4") (pin "C") (pinfunction "C_C") (pintype "passive"))
      (node (ref "U1") (pin "4") (pinfunction "A6(4,D4)_4") (pintype "bidirectional"))
    )
    (net (code "61") (name "Net-(U1-A7(6,D7,PWM))") (class "Default")
      (node (ref "D12") (pin "C") (pinfunction "C_C") (pintype "passive"))
      (node (ref "D25") (pin "C") (pinfunction "C_C") (pintype "passive"))
      (node (ref "D28") (pin "C") (pinfunction "C_C") (pintype "passive"))
      (node (ref "D35") (pin "C") (pinfunction "C_C") (pintype "passive"))
      (node (ref "D37") (pin "C") (pinfunction "C_C") (pintype "passive"))
      (node (ref "D39") (pin "C") (pinfunction "C_C") (pintype "passive"))
      (node (ref "D7") (pin "C") (pinfunction "C_C") (pintype "passive"))
      (node (ref "D8") (pin "C") (pinfunction "C_C") (pintype "passive"))
      (node (ref "U1") (pin "6") (pinfunction "A7(6,D7,PWM)_6") (pintype "bidirectional"))
    )
    (net (code "62") (name "Net-(U1-GPIO(5,C6,PWM))") (class "Default")
      (node (ref "D13") (pin "C") (pinfunction "C_C") (pintype "passive"))
      (node (ref "D18") (pin "C") (pinfunction "C_C") (pintype "passive"))
      (node (ref "D19") (pin "C") (pinfunction "C_C") (pintype "passive"))
      (node (ref "D24") (pin "C") (pinfunction "C_C") (pintype "passive"))
      (node (ref "D29") (pin "C") (pinfunction "C_C") (pintype "passive"))
      (node (ref "D34") (pin "C") (pinfunction "C_C") (pintype "passive"))
      (node (ref "D5") (pin "C") (pinfunction "C_C") (pintype "passive"))
      (node (ref "D6") (pin "C") (pinfunction "C_C") (pintype "passive"))
      (node (ref "U1") (pin "5") (pinfunction "GPIO(5,C6,PWM)_5") (pintype "bidirectional"))
    )
    (net (code "63") (name "Net-(U1-GPIO(7,E6))") (class "Default")
      (node (ref "D10") (pin "C") (pinfunction "C_C") (pintype "passive"))
      (node (ref "D11") (pin "C") (pinfunction "C_C") (pintype "passive"))
      (node (ref "D26") (pin "C") (pinfunction "C_C") (pintype "passive"))
      (node (ref "D27") (pin "C") (pinfunction "C_C") (pintype "passive"))
      (node (ref "D36") (pin "C") (pinfunction "C_C") (pintype "passive"))
      (node (ref "D40") (pin "C") (pinfunction "C_C") (pintype "passive"))
      (node (ref "D9") (pin "C") (pinfunction "C_C") (pintype "passive"))
      (node (ref "U1") (pin "7") (pinfunction "GPIO(7,E6)_7") (pintype "bidirectional"))
    )
    (net (code "64") (name "Net-(U1-RX(0,D3))") (class "Default")
      (node (ref "RGB8") (pin "DIN") (pinfunction "DIN_DIN") (pintype "input"))
      (node (ref "U1") (pin "0") (pinfunction "RX(0,D3)_0") (pintype "bidirectional"))
    )
    (net (code "65") (name "Net-(U1-SCL(3,D0,PWM))") (class "Default")
      (node (ref "SV1") (pin "2") (pinfunction "2_2") (pintype "passive"))
      (node (ref "U1") (pin "3") (pinfunction "SCL(3,D0,PWM)_3") (pintype "bidirectional"))
    )
    (net (code "66") (name "Net-(U1-TX(1,D2))") (class "Default")
      (node (ref "RGB1") (pin "VDD") (pinfunction "VDD_VDD") (pintype "bidirectional"))
      (node (ref "RGB2") (pin "VDD") (pinfunction "VDD_VDD") (pintype "bidirectional"))
      (node (ref "RGB3") (pin "VDD") (pinfunction "VDD_VDD") (pintype "bidirectional"))
      (node (ref "RGB4") (pin "VDD") (pinfunction "VDD_VDD") (pintype "bidirectional"))
      (node (ref "RGB5") (pin "VDD") (pinfunction "VDD_VDD") (pintype "bidirectional"))
      (node (ref "RGB6") (pin "VDD") (pinfunction "VDD_VDD") (pintype "bidirectional"))
      (node (ref "RGB7") (pin "VDD") (pinfunction "VDD_VDD") (pintype "bidirectional"))
      (node (ref "RGB8") (pin "VDD") (pinfunction "VDD_VDD") (pintype "bidirectional"))
      (node (ref "RGB9") (pin "VDD") (pinfunction "VDD_VDD") (pintype "bidirectional"))
      (node (ref "SV1") (pin "1") (pinfunction "1_1") (pintype "passive"))
      (node (ref "U1") (pin "1") (pinfunction "TX(1,D2)_1") (pintype "bidirectional"))
      (node (ref "U1") (pin "RAW") (pinfunction "RAW_RAW") (pintype "bidirectional"))
    )
    (net (code "67") (name "unconnected-(RGB9-PadDOUT)") (class "Default")
      (node (ref "RGB9") (pin "DOUT") (pinfunction "DOUT_DOUT") (pintype "output"))
    )
    (net (code "68") (name "unconnected-(U1-GND-PadGND@3)") (class "Default")
      (node (ref "U1") (pin "GND@3") (pinfunction "GND_GND@3") (pintype "bidirectional"))
    )
    (net (code "69") (name "unconnected-(U1-GND-PadGND@4)") (class "Default")
      (node (ref "U1") (pin "GND@4") (pinfunction "GND_GND@4") (pintype "bidirectional"))
    )
    (net (code "70") (name "unconnected-(U1-PadRST)") (class "Default")
      (node (ref "U1") (pin "RST") (pinfunction "RST_RST") (pintype "bidirectional"))
    )
    (net (code "71") (name "unconnected-(U1-PadVCC)") (class "Default")
      (node (ref "U1") (pin "VCC") (pinfunction "VCC_VCC") (pintype "bidirectional"))
    )
    (net (code "72") (name "unconnected-(U1-SDA(2,D1)-Pad2)") (class "Default")
      (node (ref "U1") (pin "2") (pinfunction "SDA(2,D1)_2") (pintype "bidirectional"))
    )
  )
)
